# S_dktriac.net
KiCad netlist of a schematic drawn in Altium Designer
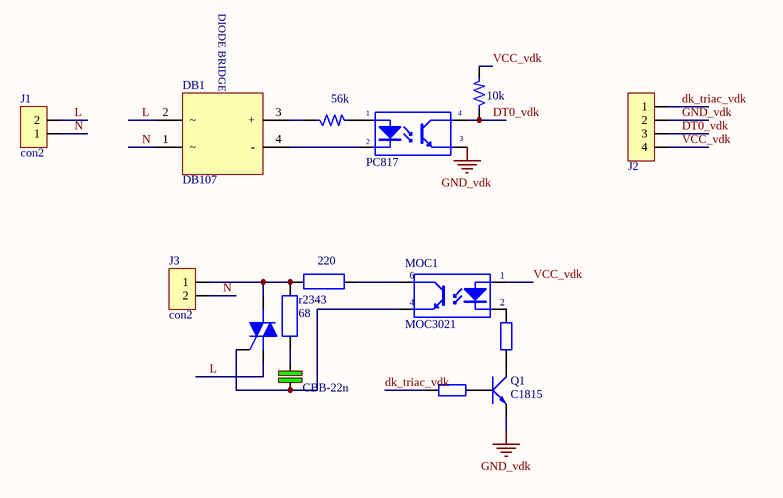
[diagram p0: S_dktriac.SchDoc]

(export (version "E")
  (design (tool "Eeschema 10.0.6"))
  (components
    (comp (ref "C123")
      (value "CBB-22n")
      (footprint "My Library:CAP_MICA_10MM")
      (description "Cap np  1pF - 472pF")
      (libsource (lib "My Library") (part "CAP"))
    )
    (comp (ref "DB1") (value "DB107") (footprint "DB107") (libsource (lib "ThinhNguyenLib") (part "DB107")))
    (comp (ref "J1") (value "con2") (footprint "Con2") (libsource (lib "Schlib1") (part "con2")))
    (comp (ref "J2")
      (value "Jum4x1_2.54")
      (footprint "Jum4Ð_2.54")
      (libsource (lib "Schlib1") (part "Jum4x1_2.54"))
    )
    (comp (ref "J3") (value "con2") (footprint "Con2") (libsource (lib "") (part "con2_1")))
    (comp (ref "MOC1")
      (value "MOC3021")
      (footprint "DIP6")
      (description "Single Opto")
      (libsource (lib "My Library") (part "MOC3021_1"))
    )
    (comp (ref "OP1") (value "PC817") (footprint "PC817-dip") (libsource (lib "Schlib1") (part "PC817")))
    (comp (ref "Q1")
      (value "C1815")
      (footprint "SOT23-321")
      (description "NPN 600mW, ECB")
      (libsource (lib "Cty1") (part "C1815"))
    )
    (comp (ref "R1") (value "10k") (footprint "0805") (libsource (lib "Schlib1") (part "res_0805")))
    (comp (ref "R2") (value "56k") (footprint "0805") (libsource (lib "Schlib1") (part "res_0805")))
    (comp (ref "R3")
      (value "220")
      (footprint "RES_SMD_0805")
      (description "Resistor 1W")
      (libsource (lib "My Library") (part "R1W"))
    )
    (comp (ref "R4")
      (value "1k")
      (footprint "DIEN TRO 0805")
      (description "Resistor SMD 0805")
      (fields (field (name "PUBLISHER") "Altium Limited"))
      (libsource (lib "") (part "R0805_1"))
    )
    (comp (ref "R5")
      (value "1k")
      (footprint "DIEN TRO 0805")
      (description "Resistor SMD 0805")
      (fields (field (name "PUBLISHER") "Altium Limited"))
      (libsource (lib "My Library") (part "R0805"))
    )
    (comp (ref "r2343")
      (value "68")
      (footprint "R1W")
      (description "Resistor 1W")
      (libsource (lib "My Library") (part "R1W"))
    )
    (comp (ref "TR1")
      (value "BTA12-600")
      (footprint "BTA6-600")
      (description "Silicon Bidirectional Triode Thyristor")
      (fields (field (name "PUBLISHER") "Altium Limited"))
      (libsource (lib "My Library") (part "BTA12-600"))
    )
  )
  (nets
    (net (code "1") (name "/DT0_vdk") (class "Default")
      (node (ref "J2") (pin "3") (pinfunction "3_3") (pintype "passive"))
      (node (ref "OP1") (pin "4") (pinfunction "C_4") (pintype "passive"))
      (node (ref "R1") (pin "1") (pinfunction "1_1") (pintype "passive"))
    )
    (net (code "2") (name "/L") (class "Default")
      (node (ref "DB1") (pin "2") (pinfunction "~_2") (pintype "passive"))
      (node (ref "J1") (pin "2") (pinfunction "2_2") (pintype "passive"))
      (node (ref "TR1") (pin "1") (pinfunction "M1_1") (pintype "passive"))
    )
    (net (code "3") (name "/N") (class "Default")
      (node (ref "DB1") (pin "1") (pinfunction "~_1") (pintype "passive"))
      (node (ref "J1") (pin "1") (pinfunction "1_1") (pintype "passive"))
      (node (ref "J3") (pin "2") (pinfunction "2_2") (pintype "passive"))
    )
    (net (code "4") (name "/VCC_vdk") (class "Default")
      (node (ref "J2") (pin "4") (pinfunction "4_4") (pintype "passive"))
      (node (ref "MOC1") (pin "1") (pinfunction "A_1") (pintype "passive"))
      (node (ref "R1") (pin "2") (pinfunction "2_2") (pintype "passive"))
    )
    (net (code "5") (name "/dk_triac_vdk") (class "Default")
      (node (ref "J2") (pin "1") (pinfunction "1_1") (pintype "passive"))
      (node (ref "R5") (pin "2") (pinfunction "2_2") (pintype "passive"))
    )
    (net (code "6") (name "GND_vdk") (class "Default")
      (node (ref "J2") (pin "2") (pinfunction "2_2") (pintype "passive"))
      (node (ref "OP1") (pin "3") (pinfunction "E_3") (pintype "passive"))
      (node (ref "Q1") (pin "1") (pinfunction "E_1") (pintype "passive"))
    )
    (net (code "7") (name "Net-(C123-Pad2)") (class "Default")
      (node (ref "C123") (pin "2") (pinfunction "2_2") (pintype "passive"))
      (node (ref "r2343") (pin "1") (pinfunction "1_1") (pintype "passive"))
    )
    (net (code "8") (name "Net-(DB1-+)") (class "Default")
      (node (ref "DB1") (pin "3") (pinfunction "+_3") (pintype "passive"))
      (node (ref "R2") (pin "1") (pinfunction "1_1") (pintype "passive"))
    )
    (net (code "9") (name "Net-(DB1--)") (class "Default")
      (node (ref "DB1") (pin "4") (pinfunction "-_4") (pintype "passive"))
      (node (ref "OP1") (pin "2") (pinfunction "K_2") (pintype "passive"))
    )
    (net (code "10") (name "Net-(MOC1-C)") (class "Default")
      (node (ref "MOC1") (pin "6") (pinfunction "C_6") (pintype "passive"))
      (node (ref "R3") (pin "2") (pinfunction "2_2") (pintype "passive"))
    )
    (net (code "11") (name "Net-(MOC1-E)") (class "Default")
      (node (ref "C123") (pin "1") (pinfunction "1_1") (pintype "passive"))
      (node (ref "MOC1") (pin "4") (pinfunction "E_4") (pintype "passive"))
      (node (ref "TR1") (pin "3") (pinfunction "G_3") (pintype "passive"))
    )
    (net (code "12") (name "Net-(MOC1-K)") (class "Default")
      (node (ref "MOC1") (pin "2") (pinfunction "K_2") (pintype "passive"))
      (node (ref "R4") (pin "2") (pinfunction "2_2") (pintype "passive"))
    )
    (net (code "13") (name "Net-(OP1-A)") (class "Default")
      (node (ref "OP1") (pin "1") (pinfunction "A_1") (pintype "passive"))
      (node (ref "R2") (pin "2") (pinfunction "2_2") (pintype "passive"))
    )
    (net (code "14") (name "Net-(Q1-B)") (class "Default")
      (node (ref "Q1") (pin "3") (pinfunction "B_3") (pintype "passive"))
      (node (ref "R5") (pin "1") (pinfunction "1_1") (pintype "passive"))
    )
    (net (code "15") (name "Net-(Q1-C)") (class "Default")
      (node (ref "Q1") (pin "2") (pinfunction "C_2") (pintype "passive"))
      (node (ref "R4") (pin "1") (pinfunction "1_1") (pintype "passive"))
    )
    (net (code "16") (name "Net-(TR1-M2)") (class "Default")
      (node (ref "J3") (pin "1") (pinfunction "1_1") (pintype "passive"))
      (node (ref "R3") (pin "1") (pinfunction "1_1") (pintype "passive"))
      (node (ref "TR1") (pin "2") (pinfunction "M2_2") (pintype "passive"))
      (node (ref "r2343") (pin "2") (pinfunction "2_2") (pintype "passive"))
    )
  )
)
